# MCP23017_Aufsatz_Verzweiger_V2_1.net
KiCad netlist of a schematic drawn in EAGLE
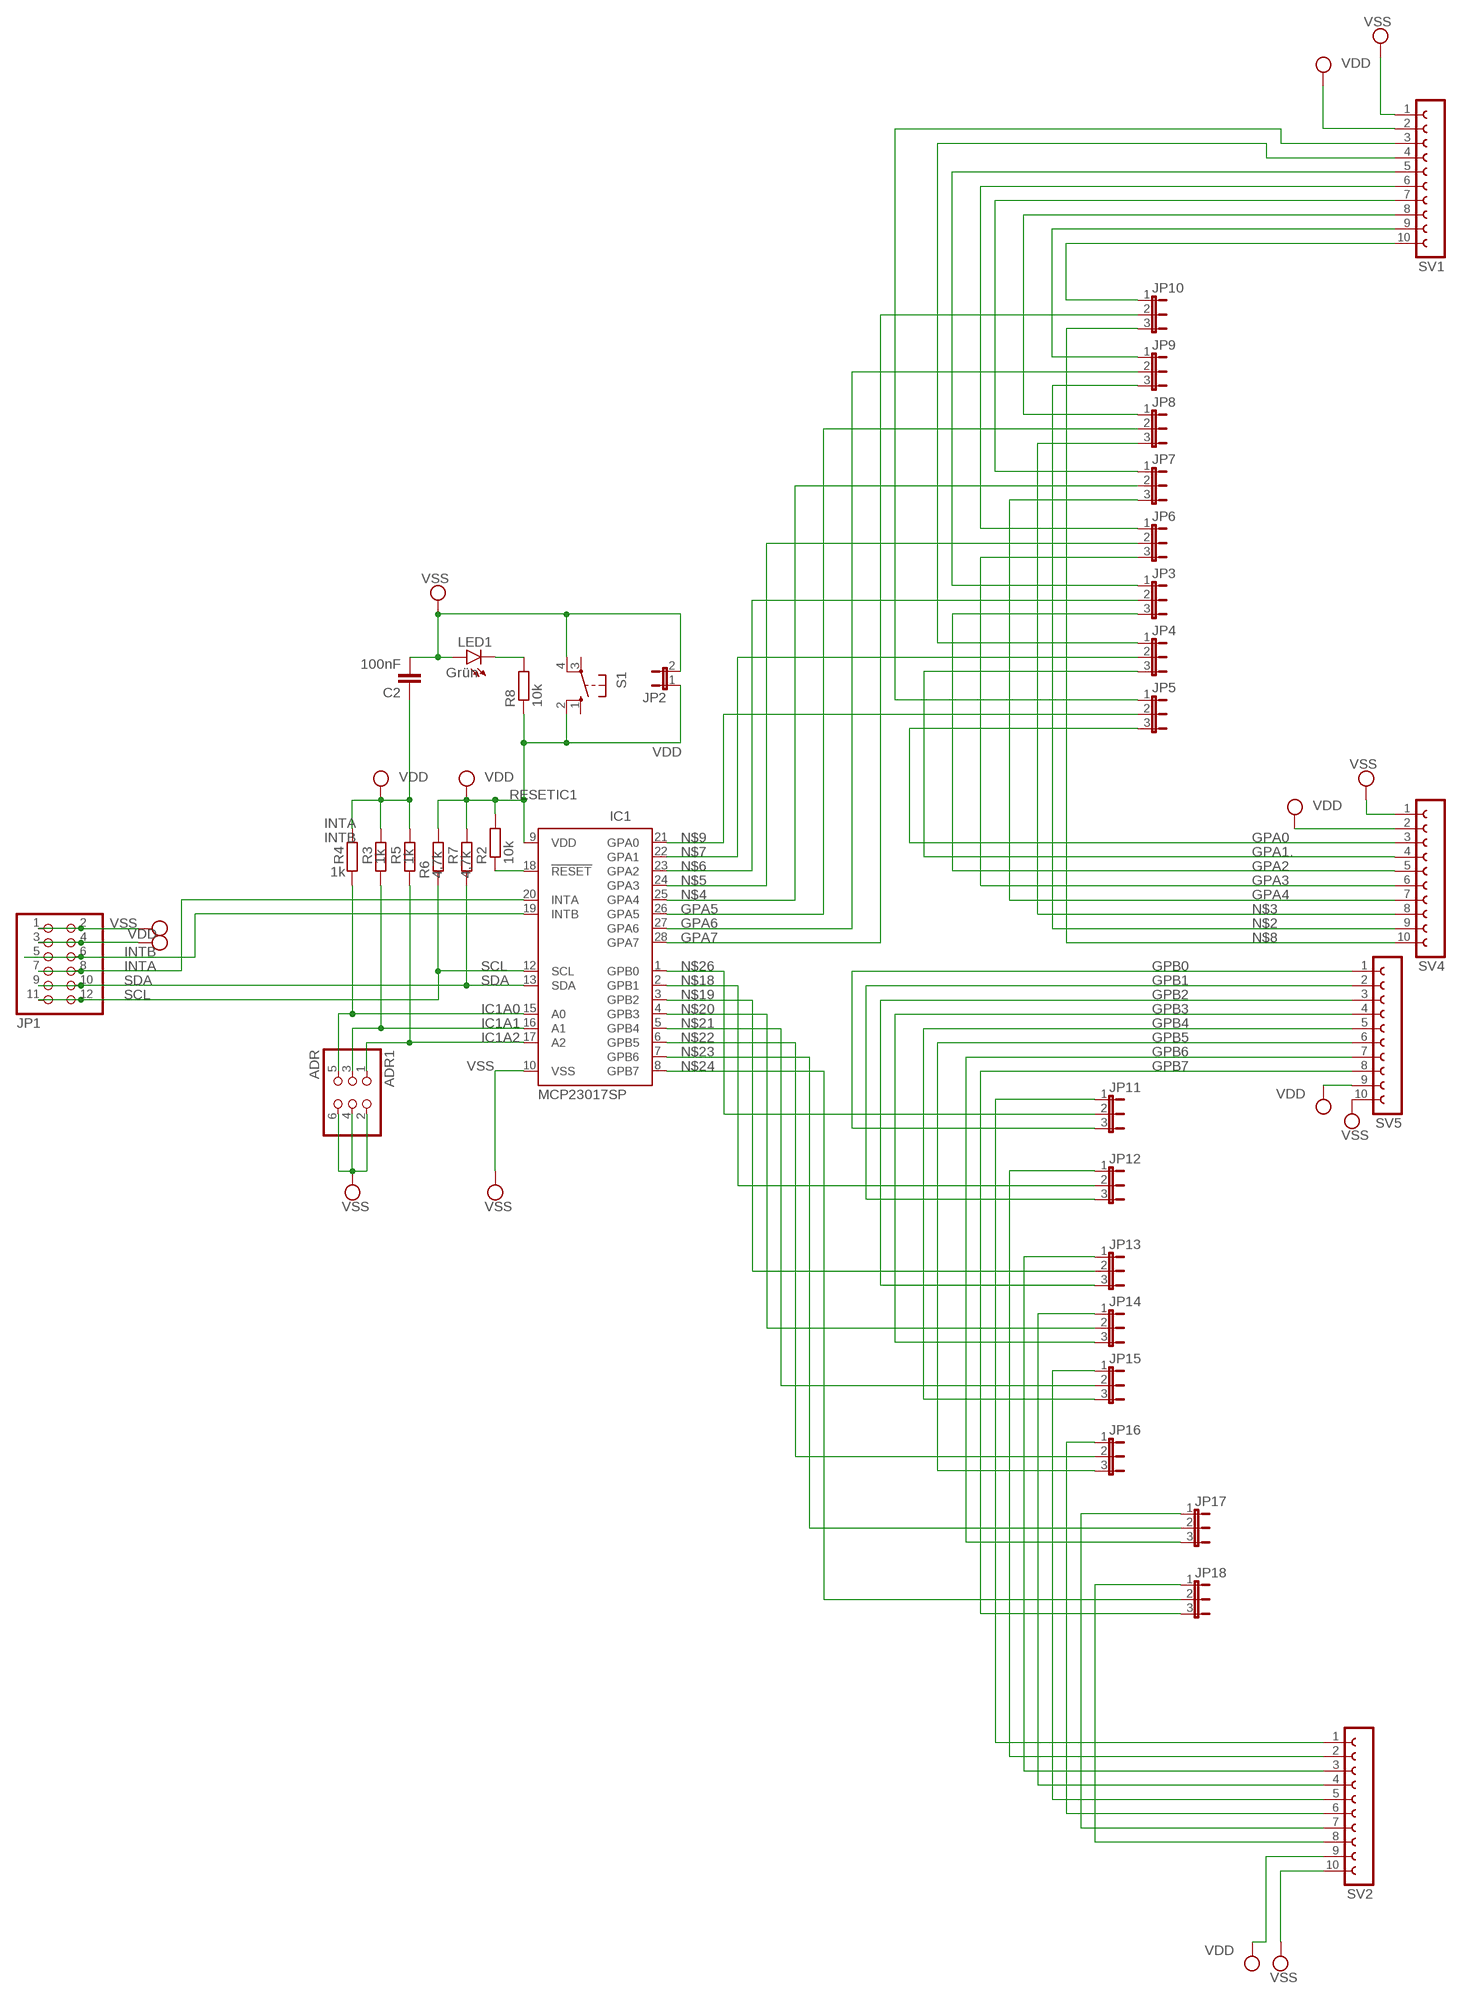
[diagram p0: schematic, sheet 1]

(export (version "E")
  (design (tool "Eeschema 10.0.6"))
  (components
    (comp (ref "ADR1")
      (value "ADR")
      (footprint "eagle-import:2X03")
      (libsource (lib "eagle-import") (part "PINHD-2X3"))
    )
    (comp (ref "C2")
      (value "100nF")
      (footprint "eagle-import:C025-025X050")
      (libsource (lib "eagle-import") (part "C-EU025-025X050"))
    )
    (comp (ref "IC1")
      (value "MCP23017SP")
      (footprint "eagle-import:DIL28-3")
      (fields (field (name "MF") "MICROCHIP") (field (name "MPN") "MCP23017-E/SP"))
      (libsource (lib "eagle-import") (part "MCP23017SP"))
    )
    (comp (ref "JP1")
      (value "JP1")
      (footprint "eagle-import:2X06_90")
      (libsource (lib "eagle-import") (part "PINHD-2X6/90"))
    )
    (comp (ref "JP2")
      (value "JP1E")
      (footprint "eagle-import:JP1")
      (libsource (lib "eagle-import") (part "JP1E"))
    )
    (comp (ref "JP3")
      (value "JP2E")
      (footprint "eagle-import:JP2")
      (libsource (lib "eagle-import") (part "JP2E"))
    )
    (comp (ref "JP4")
      (value "JP2E")
      (footprint "eagle-import:JP2")
      (libsource (lib "eagle-import") (part "JP2E"))
    )
    (comp (ref "JP5")
      (value "JP2E")
      (footprint "eagle-import:JP2")
      (libsource (lib "eagle-import") (part "JP2E"))
    )
    (comp (ref "JP6")
      (value "JP2E")
      (footprint "eagle-import:JP2")
      (libsource (lib "eagle-import") (part "JP2E"))
    )
    (comp (ref "JP7")
      (value "JP2E")
      (footprint "eagle-import:JP2")
      (libsource (lib "eagle-import") (part "JP2E"))
    )
    (comp (ref "JP8")
      (value "JP2E")
      (footprint "eagle-import:JP2")
      (libsource (lib "eagle-import") (part "JP2E"))
    )
    (comp (ref "JP9")
      (value "JP2E")
      (footprint "eagle-import:JP2")
      (libsource (lib "eagle-import") (part "JP2E"))
    )
    (comp (ref "JP10")
      (value "JP2E")
      (footprint "eagle-import:JP2")
      (libsource (lib "eagle-import") (part "JP2E"))
    )
    (comp (ref "JP11")
      (value "JP2E")
      (footprint "eagle-import:JP2")
      (libsource (lib "eagle-import") (part "JP2E"))
    )
    (comp (ref "JP12")
      (value "JP2E")
      (footprint "eagle-import:JP2")
      (libsource (lib "eagle-import") (part "JP2E"))
    )
    (comp (ref "JP13")
      (value "JP2E")
      (footprint "eagle-import:JP2")
      (libsource (lib "eagle-import") (part "JP2E"))
    )
    (comp (ref "JP14")
      (value "JP2E")
      (footprint "eagle-import:JP2")
      (libsource (lib "eagle-import") (part "JP2E"))
    )
    (comp (ref "JP15")
      (value "JP2E")
      (footprint "eagle-import:JP2")
      (libsource (lib "eagle-import") (part "JP2E"))
    )
    (comp (ref "JP16")
      (value "JP2E")
      (footprint "eagle-import:JP2")
      (libsource (lib "eagle-import") (part "JP2E"))
    )
    (comp (ref "JP17")
      (value "JP2E")
      (footprint "eagle-import:JP2")
      (libsource (lib "eagle-import") (part "JP2E"))
    )
    (comp (ref "JP18")
      (value "JP2E")
      (footprint "eagle-import:JP2")
      (libsource (lib "eagle-import") (part "JP2E"))
    )
    (comp (ref "LED1")
      (value "Grün")
      (footprint "eagle-import:LED3MM")
      (libsource (lib "eagle-import") (part "LED3MM"))
    )
    (comp (ref "R2")
      (value "10k")
      (footprint "eagle-import:0207_10")
      (libsource (lib "eagle-import") (part "R-EU_0207/10"))
    )
    (comp (ref "R3")
      (value "1k")
      (footprint "eagle-import:0207_10")
      (libsource (lib "eagle-import") (part "R-EU_0207/10"))
    )
    (comp (ref "R4")
      (value "1k")
      (footprint "eagle-import:0207_10")
      (libsource (lib "eagle-import") (part "R-EU_0207/10"))
    )
    (comp (ref "R5")
      (value "1k")
      (footprint "eagle-import:0207_10")
      (libsource (lib "eagle-import") (part "R-EU_0207/10"))
    )
    (comp (ref "R6")
      (value "4,7k")
      (footprint "eagle-import:0207_10")
      (libsource (lib "eagle-import") (part "R-EU_0207/10"))
    )
    (comp (ref "R7")
      (value "4,7k")
      (footprint "eagle-import:0207_10")
      (libsource (lib "eagle-import") (part "R-EU_0207/10"))
    )
    (comp (ref "R8")
      (value "10k")
      (footprint "eagle-import:0207_10")
      (libsource (lib "eagle-import") (part "R-EU_0207/10"))
    )
    (comp (ref "S1")
      (value "10-XX")
      (footprint "eagle-import:B3F-10XX")
      (fields (field (name "MPN") "B3F-1000"))
      (libsource (lib "eagle-import") (part "10-XX"))
    )
    (comp (ref "SV1")
      (value "FE10-1")
      (footprint "eagle-import:FE10")
      (libsource (lib "eagle-import") (part "FE10-1"))
    )
    (comp (ref "SV2")
      (value "FE10-1")
      (footprint "eagle-import:FE10")
      (libsource (lib "eagle-import") (part "FE10-1"))
    )
    (comp (ref "SV4")
      (value "FE10-1")
      (footprint "eagle-import:FE10")
      (libsource (lib "eagle-import") (part "FE10-1"))
    )
    (comp (ref "SV5")
      (value "FE10-1")
      (footprint "eagle-import:FE10")
      (libsource (lib "eagle-import") (part "FE10-1"))
    )
  )
  (nets
    (net (code "1") (name "/GPA0") (class "Default")
      (node (ref "JP5") (pin "3") (pinfunction "3_3") (pintype "passive"))
      (node (ref "SV4") (pin "3") (pinfunction "3_3") (pintype "passive"))
    )
    (net (code "2") (name "/GPA1.") (class "Default")
      (node (ref "JP4") (pin "3") (pinfunction "3_3") (pintype "passive"))
      (node (ref "SV4") (pin "4") (pinfunction "4_4") (pintype "passive"))
    )
    (net (code "3") (name "/GPA2") (class "Default")
      (node (ref "JP3") (pin "3") (pinfunction "3_3") (pintype "passive"))
      (node (ref "SV4") (pin "5") (pinfunction "5_5") (pintype "passive"))
    )
    (net (code "4") (name "/GPA3") (class "Default")
      (node (ref "JP6") (pin "3") (pinfunction "3_3") (pintype "passive"))
      (node (ref "SV4") (pin "6") (pinfunction "6_6") (pintype "passive"))
    )
    (net (code "5") (name "/GPA4") (class "Default")
      (node (ref "JP7") (pin "3") (pinfunction "3_3") (pintype "passive"))
      (node (ref "SV4") (pin "7") (pinfunction "7_7") (pintype "passive"))
    )
    (net (code "6") (name "/GPA5") (class "Default")
      (node (ref "IC1") (pin "26") (pinfunction "GPA5_26") (pintype "bidirectional"))
      (node (ref "JP8") (pin "2") (pinfunction "2_2") (pintype "passive"))
    )
    (net (code "7") (name "/GPA6") (class "Default")
      (node (ref "IC1") (pin "27") (pinfunction "GPA6_27") (pintype "bidirectional"))
      (node (ref "JP9") (pin "2") (pinfunction "2_2") (pintype "passive"))
    )
    (net (code "8") (name "/GPA7") (class "Default")
      (node (ref "IC1") (pin "28") (pinfunction "GPA7_28") (pintype "bidirectional"))
      (node (ref "JP10") (pin "2") (pinfunction "2_2") (pintype "passive"))
    )
    (net (code "9") (name "/GPB0") (class "Default")
      (node (ref "JP11") (pin "3") (pinfunction "3_3") (pintype "passive"))
      (node (ref "SV5") (pin "1") (pinfunction "1_1") (pintype "passive"))
    )
    (net (code "10") (name "/GPB1") (class "Default")
      (node (ref "JP12") (pin "3") (pinfunction "3_3") (pintype "passive"))
      (node (ref "SV5") (pin "2") (pinfunction "2_2") (pintype "passive"))
    )
    (net (code "11") (name "/GPB2") (class "Default")
      (node (ref "JP13") (pin "3") (pinfunction "3_3") (pintype "passive"))
      (node (ref "SV5") (pin "3") (pinfunction "3_3") (pintype "passive"))
    )
    (net (code "12") (name "/GPB3") (class "Default")
      (node (ref "JP14") (pin "3") (pinfunction "3_3") (pintype "passive"))
      (node (ref "SV5") (pin "4") (pinfunction "4_4") (pintype "passive"))
    )
    (net (code "13") (name "/GPB4") (class "Default")
      (node (ref "JP15") (pin "3") (pinfunction "3_3") (pintype "passive"))
      (node (ref "SV5") (pin "5") (pinfunction "5_5") (pintype "passive"))
    )
    (net (code "14") (name "/GPB5") (class "Default")
      (node (ref "JP16") (pin "3") (pinfunction "3_3") (pintype "passive"))
      (node (ref "SV5") (pin "6") (pinfunction "6_6") (pintype "passive"))
    )
    (net (code "15") (name "/GPB6") (class "Default")
      (node (ref "JP17") (pin "3") (pinfunction "3_3") (pintype "passive"))
      (node (ref "SV5") (pin "7") (pinfunction "7_7") (pintype "passive"))
    )
    (net (code "16") (name "/GPB7") (class "Default")
      (node (ref "JP18") (pin "3") (pinfunction "3_3") (pintype "passive"))
      (node (ref "SV5") (pin "8") (pinfunction "8_8") (pintype "passive"))
    )
    (net (code "17") (name "/IC1A0") (class "Default")
      (node (ref "ADR1") (pin "5") (pinfunction "5_5") (pintype "passive"))
      (node (ref "IC1") (pin "15") (pinfunction "A0_15") (pintype "input"))
      (node (ref "R4") (pin "1") (pinfunction "1_1") (pintype "passive"))
    )
    (net (code "18") (name "/IC1A1") (class "Default")
      (node (ref "ADR1") (pin "3") (pinfunction "3_3") (pintype "passive"))
      (node (ref "IC1") (pin "16") (pinfunction "A1_16") (pintype "input"))
      (node (ref "R3") (pin "1") (pinfunction "1_1") (pintype "passive"))
    )
    (net (code "19") (name "/IC1A2") (class "Default")
      (node (ref "ADR1") (pin "1") (pinfunction "1_1") (pintype "passive"))
      (node (ref "IC1") (pin "17") (pinfunction "A2_17") (pintype "input"))
      (node (ref "R5") (pin "1") (pinfunction "1_1") (pintype "passive"))
    )
    (net (code "20") (name "/INTA") (class "Default")
      (node (ref "IC1") (pin "20") (pinfunction "INTA_20") (pintype "output"))
      (node (ref "JP1") (pin "7") (pinfunction "7_7") (pintype "passive"))
      (node (ref "JP1") (pin "8") (pinfunction "8_8") (pintype "passive"))
    )
    (net (code "21") (name "/INTB") (class "Default")
      (node (ref "IC1") (pin "19") (pinfunction "INTB_19") (pintype "output"))
      (node (ref "JP1") (pin "5") (pinfunction "5_5") (pintype "passive"))
      (node (ref "JP1") (pin "6") (pinfunction "6_6") (pintype "passive"))
    )
    (net (code "22") (name "/N$2") (class "Default")
      (node (ref "JP9") (pin "3") (pinfunction "3_3") (pintype "passive"))
      (node (ref "SV4") (pin "9") (pinfunction "9_9") (pintype "passive"))
    )
    (net (code "23") (name "/N$3") (class "Default")
      (node (ref "JP8") (pin "3") (pinfunction "3_3") (pintype "passive"))
      (node (ref "SV4") (pin "8") (pinfunction "8_8") (pintype "passive"))
    )
    (net (code "24") (name "/N$4") (class "Default")
      (node (ref "IC1") (pin "25") (pinfunction "GPA4_25") (pintype "bidirectional"))
      (node (ref "JP7") (pin "2") (pinfunction "2_2") (pintype "passive"))
    )
    (net (code "25") (name "/N$5") (class "Default")
      (node (ref "IC1") (pin "24") (pinfunction "GPA3_24") (pintype "bidirectional"))
      (node (ref "JP6") (pin "2") (pinfunction "2_2") (pintype "passive"))
    )
    (net (code "26") (name "/N$6") (class "Default")
      (node (ref "IC1") (pin "23") (pinfunction "GPA2_23") (pintype "bidirectional"))
      (node (ref "JP3") (pin "2") (pinfunction "2_2") (pintype "passive"))
    )
    (net (code "27") (name "/N$7") (class "Default")
      (node (ref "IC1") (pin "22") (pinfunction "GPA1_22") (pintype "bidirectional"))
      (node (ref "JP4") (pin "2") (pinfunction "2_2") (pintype "passive"))
    )
    (net (code "28") (name "/N$8") (class "Default")
      (node (ref "JP10") (pin "3") (pinfunction "3_3") (pintype "passive"))
      (node (ref "SV4") (pin "10") (pinfunction "10_10") (pintype "passive"))
    )
    (net (code "29") (name "/N$9") (class "Default")
      (node (ref "IC1") (pin "21") (pinfunction "GPA0_21") (pintype "bidirectional"))
      (node (ref "JP5") (pin "2") (pinfunction "2_2") (pintype "passive"))
    )
    (net (code "30") (name "/N$18") (class "Default")
      (node (ref "IC1") (pin "2") (pinfunction "GPB1_2") (pintype "bidirectional"))
      (node (ref "JP12") (pin "2") (pinfunction "2_2") (pintype "passive"))
    )
    (net (code "31") (name "/N$19") (class "Default")
      (node (ref "IC1") (pin "3") (pinfunction "GPB2_3") (pintype "bidirectional"))
      (node (ref "JP13") (pin "2") (pinfunction "2_2") (pintype "passive"))
    )
    (net (code "32") (name "/N$20") (class "Default")
      (node (ref "IC1") (pin "4") (pinfunction "GPB3_4") (pintype "bidirectional"))
      (node (ref "JP14") (pin "2") (pinfunction "2_2") (pintype "passive"))
    )
    (net (code "33") (name "/N$21") (class "Default")
      (node (ref "IC1") (pin "5") (pinfunction "GPB4_5") (pintype "bidirectional"))
      (node (ref "JP15") (pin "2") (pinfunction "2_2") (pintype "passive"))
    )
    (net (code "34") (name "/N$22") (class "Default")
      (node (ref "IC1") (pin "6") (pinfunction "GPB5_6") (pintype "bidirectional"))
      (node (ref "JP16") (pin "2") (pinfunction "2_2") (pintype "passive"))
    )
    (net (code "35") (name "/N$23") (class "Default")
      (node (ref "IC1") (pin "7") (pinfunction "GPB6_7") (pintype "bidirectional"))
      (node (ref "JP17") (pin "2") (pinfunction "2_2") (pintype "passive"))
    )
    (net (code "36") (name "/N$24") (class "Default")
      (node (ref "IC1") (pin "8") (pinfunction "GPB7_8") (pintype "bidirectional"))
      (node (ref "JP18") (pin "2") (pinfunction "2_2") (pintype "passive"))
    )
    (net (code "37") (name "/N$26") (class "Default")
      (node (ref "IC1") (pin "1") (pinfunction "GPB0_1") (pintype "bidirectional"))
      (node (ref "JP11") (pin "2") (pinfunction "2_2") (pintype "passive"))
    )
    (net (code "38") (name "/RESETIC1") (class "Default")
      (node (ref "IC1") (pin "18") (pinfunction "~{RESET}_18") (pintype "input"))
      (node (ref "R2") (pin "1") (pinfunction "1_1") (pintype "passive"))
    )
    (net (code "39") (name "/SCL") (class "Default")
      (node (ref "IC1") (pin "12") (pinfunction "SCL_12") (pintype "input"))
      (node (ref "JP1") (pin "11") (pinfunction "11_11") (pintype "passive"))
      (node (ref "JP1") (pin "12") (pinfunction "12_12") (pintype "passive"))
      (node (ref "R6") (pin "1") (pinfunction "1_1") (pintype "passive"))
    )
    (net (code "40") (name "/SDA") (class "Default")
      (node (ref "IC1") (pin "13") (pinfunction "SDA_13") (pintype "bidirectional"))
      (node (ref "JP1") (pin "10") (pinfunction "10_10") (pintype "passive"))
      (node (ref "JP1") (pin "9") (pinfunction "9_9") (pintype "passive"))
      (node (ref "R7") (pin "1") (pinfunction "1_1") (pintype "passive"))
    )
    (net (code "41") (name "Net-(JP3-Pad1)") (class "Default")
      (node (ref "JP3") (pin "1") (pinfunction "1_1") (pintype "passive"))
      (node (ref "SV1") (pin "5") (pinfunction "5_5") (pintype "passive"))
    )
    (net (code "42") (name "Net-(JP4-Pad1)") (class "Default")
      (node (ref "JP4") (pin "1") (pinfunction "1_1") (pintype "passive"))
      (node (ref "SV1") (pin "4") (pinfunction "4_4") (pintype "passive"))
    )
    (net (code "43") (name "Net-(JP5-Pad1)") (class "Default")
      (node (ref "JP5") (pin "1") (pinfunction "1_1") (pintype "passive"))
      (node (ref "SV1") (pin "3") (pinfunction "3_3") (pintype "passive"))
    )
    (net (code "44") (name "Net-(JP6-Pad1)") (class "Default")
      (node (ref "JP6") (pin "1") (pinfunction "1_1") (pintype "passive"))
      (node (ref "SV1") (pin "6") (pinfunction "6_6") (pintype "passive"))
    )
    (net (code "45") (name "Net-(JP7-Pad1)") (class "Default")
      (node (ref "JP7") (pin "1") (pinfunction "1_1") (pintype "passive"))
      (node (ref "SV1") (pin "7") (pinfunction "7_7") (pintype "passive"))
    )
    (net (code "46") (name "Net-(JP8-Pad1)") (class "Default")
      (node (ref "JP8") (pin "1") (pinfunction "1_1") (pintype "passive"))
      (node (ref "SV1") (pin "8") (pinfunction "8_8") (pintype "passive"))
    )
    (net (code "47") (name "Net-(JP9-Pad1)") (class "Default")
      (node (ref "JP9") (pin "1") (pinfunction "1_1") (pintype "passive"))
      (node (ref "SV1") (pin "9") (pinfunction "9_9") (pintype "passive"))
    )
    (net (code "48") (name "Net-(JP10-Pad1)") (class "Default")
      (node (ref "JP10") (pin "1") (pinfunction "1_1") (pintype "passive"))
      (node (ref "SV1") (pin "10") (pinfunction "10_10") (pintype "passive"))
    )
    (net (code "49") (name "Net-(JP11-Pad1)") (class "Default")
      (node (ref "JP11") (pin "1") (pinfunction "1_1") (pintype "passive"))
      (node (ref "SV2") (pin "1") (pinfunction "1_1") (pintype "passive"))
    )
    (net (code "50") (name "Net-(JP12-Pad1)") (class "Default")
      (node (ref "JP12") (pin "1") (pinfunction "1_1") (pintype "passive"))
      (node (ref "SV2") (pin "2") (pinfunction "2_2") (pintype "passive"))
    )
    (net (code "51") (name "Net-(JP13-Pad1)") (class "Default")
      (node (ref "JP13") (pin "1") (pinfunction "1_1") (pintype "passive"))
      (node (ref "SV2") (pin "3") (pinfunction "3_3") (pintype "passive"))
    )
    (net (code "52") (name "Net-(JP14-Pad1)") (class "Default")
      (node (ref "JP14") (pin "1") (pinfunction "1_1") (pintype "passive"))
      (node (ref "SV2") (pin "4") (pinfunction "4_4") (pintype "passive"))
    )
    (net (code "53") (name "Net-(JP15-Pad1)") (class "Default")
      (node (ref "JP15") (pin "1") (pinfunction "1_1") (pintype "passive"))
      (node (ref "SV2") (pin "5") (pinfunction "5_5") (pintype "passive"))
    )
    (net (code "54") (name "Net-(JP16-Pad1)") (class "Default")
      (node (ref "JP16") (pin "1") (pinfunction "1_1") (pintype "passive"))
      (node (ref "SV2") (pin "6") (pinfunction "6_6") (pintype "passive"))
    )
    (net (code "55") (name "Net-(JP17-Pad1)") (class "Default")
      (node (ref "JP17") (pin "1") (pinfunction "1_1") (pintype "passive"))
      (node (ref "SV2") (pin "7") (pinfunction "7_7") (pintype "passive"))
    )
    (net (code "56") (name "Net-(JP18-Pad1)") (class "Default")
      (node (ref "JP18") (pin "1") (pinfunction "1_1") (pintype "passive"))
      (node (ref "SV2") (pin "8") (pinfunction "8_8") (pintype "passive"))
    )
    (net (code "57") (name "Net-(LED1-C)") (class "Default")
      (node (ref "LED1") (pin "K") (pinfunction "C_K") (pintype "passive"))
      (node (ref "R8") (pin "2") (pinfunction "2_2") (pintype "passive"))
    )
    (net (code "58") (name "VDD") (class "Default")
      (node (ref "C2") (pin "1") (pinfunction "1_1") (pintype "passive"))
      (node (ref "IC1") (pin "9") (pinfunction "VDD_9") (pintype "power_in"))
      (node (ref "JP1") (pin "3") (pinfunction "3_3") (pintype "passive"))
      (node (ref "JP1") (pin "4") (pinfunction "4_4") (pintype "passive"))
      (node (ref "JP2") (pin "1") (pinfunction "1_1") (pintype "passive"))
      (node (ref "R2") (pin "2") (pinfunction "2_2") (pintype "passive"))
      (node (ref "R3") (pin "2") (pinfunction "2_2") (pintype "passive"))
      (node (ref "R4") (pin "2") (pinfunction "2_2") (pintype "passive"))
      (node (ref "R5") (pin "2") (pinfunction "2_2") (pintype "passive"))
      (node (ref "R6") (pin "2") (pinfunction "2_2") (pintype "passive"))
      (node (ref "R7") (pin "2") (pinfunction "2_2") (pintype "passive"))
      (node (ref "R8") (pin "1") (pinfunction "1_1") (pintype "passive"))
      (node (ref "S1") (pin "2") (pinfunction "S1_2") (pintype "passive"))
      (node (ref "SV1") (pin "2") (pinfunction "2_2") (pintype "passive"))
      (node (ref "SV2") (pin "9") (pinfunction "9_9") (pintype "passive"))
      (node (ref "SV4") (pin "2") (pinfunction "2_2") (pintype "passive"))
      (node (ref "SV5") (pin "9") (pinfunction "9_9") (pintype "passive"))
    )
    (net (code "59") (name "VSS") (class "Default")
      (node (ref "ADR1") (pin "2") (pinfunction "2_2") (pintype "passive"))
      (node (ref "ADR1") (pin "4") (pinfunction "4_4") (pintype "passive"))
      (node (ref "ADR1") (pin "6") (pinfunction "6_6") (pintype "passive"))
      (node (ref "C2") (pin "2") (pinfunction "2_2") (pintype "passive"))
      (node (ref "IC1") (pin "10") (pinfunction "VSS_10") (pintype "power_in"))
      (node (ref "JP1") (pin "1") (pinfunction "1_1") (pintype "passive"))
      (node (ref "JP1") (pin "2") (pinfunction "2_2") (pintype "passive"))
      (node (ref "JP2") (pin "2") (pinfunction "2_2") (pintype "passive"))
      (node (ref "LED1") (pin "A") (pinfunction "A_A") (pintype "passive"))
      (node (ref "S1") (pin "4") (pinfunction "P1_4") (pintype "passive"))
      (node (ref "SV1") (pin "1") (pinfunction "1_1") (pintype "passive"))
      (node (ref "SV2") (pin "10") (pinfunction "10_10") (pintype "passive"))
      (node (ref "SV4") (pin "1") (pinfunction "1_1") (pintype "passive"))
      (node (ref "SV5") (pin "10") (pinfunction "10_10") (pintype "passive"))
    )
    (net (code "60") (name "unconnected-(S1-P-Pad3)") (class "Default")
      (node (ref "S1") (pin "3") (pinfunction "P_3") (pintype "passive"))
    )
    (net (code "61") (name "unconnected-(S1-S-Pad1)") (class "Default")
      (node (ref "S1") (pin "1") (pinfunction "S_1") (pintype "passive"))
    )
  )
)
